# untitled.net
KiCad netlist of a schematic drawn in EAGLE
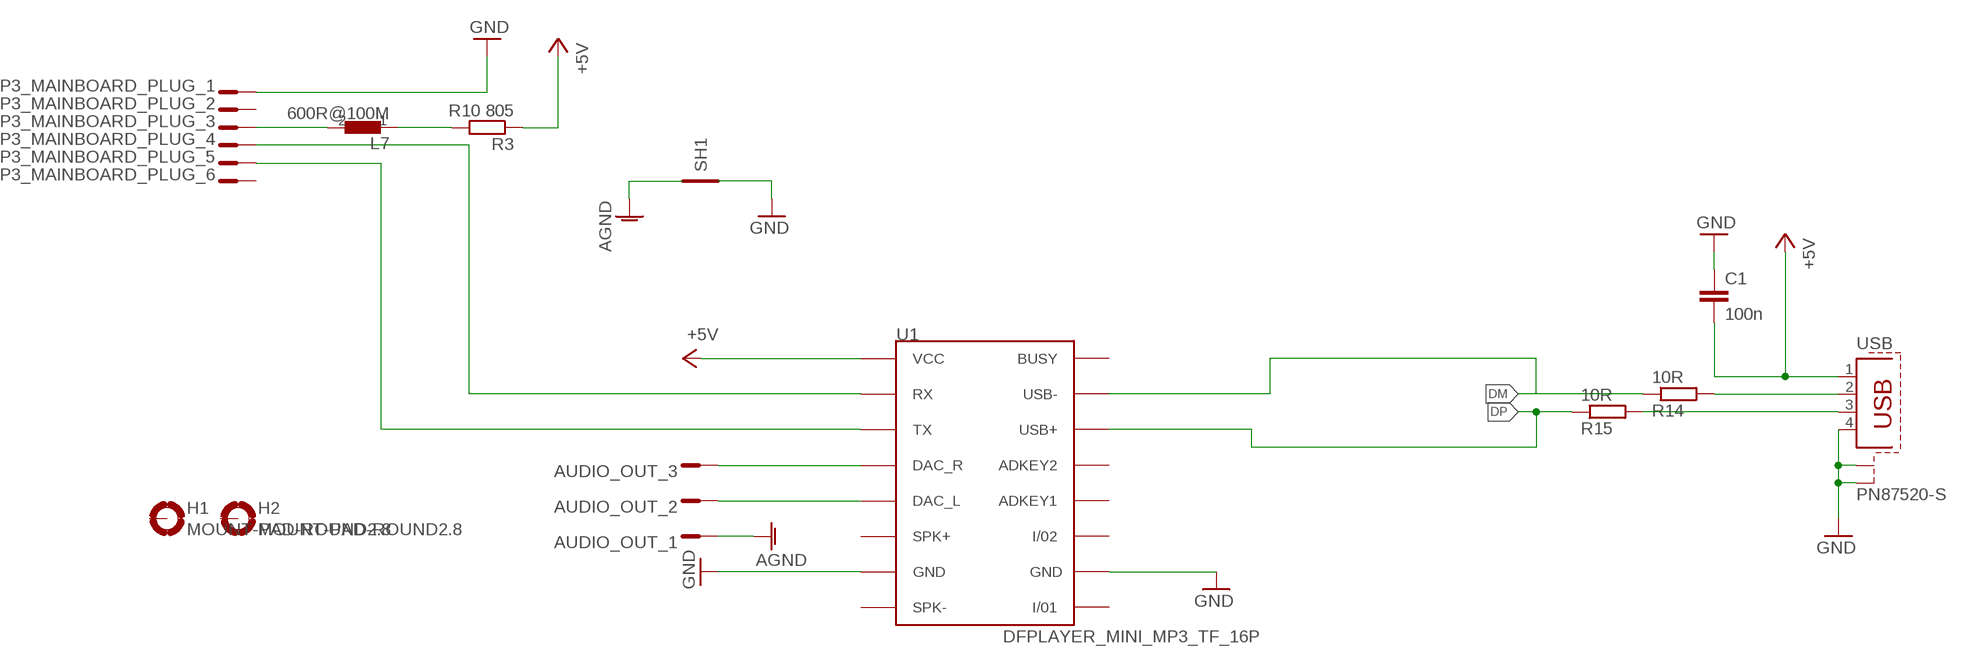
[diagram p0: schematic, sheet 1]

(export (version "E")
  (design (tool "Eeschema 10.0.6"))
  (components
    (comp (ref "AUDIO_OUT")
      (value "JST_3_PIN_B3B-PH-KS")
      (footprint "eagle-import:B3B-PH-KS")
      (libsource (lib "eagle-import") (part "JST_3_PIN_B3B-PH-KS"))
    )
    (comp (ref "C1")
      (value "100n")
      (footprint "eagle-import:C0805")
      (libsource (lib "eagle-import") (part "C-EUC0805"))
    )
    (comp (ref "H1")
      (value "MOUNT-PAD-ROUND2.8")
      (footprint "eagle-import:2,8-PAD")
      (libsource (lib "eagle-import") (part "MOUNT-PAD-ROUND2.8"))
    )
    (comp (ref "H2")
      (value "MOUNT-PAD-ROUND2.8")
      (footprint "eagle-import:2,8-PAD")
      (libsource (lib "eagle-import") (part "MOUNT-PAD-ROUND2.8"))
    )
    (comp (ref "L7")
      (value "600R@100M")
      (footprint "eagle-import:R0805")
      (libsource (lib "eagle-import") (part "FERRITR0805"))
    )
    (comp (ref "MP3_MAINBOARD_PLUG")
      (value "JST_6_PIN_B6B-PH-KS")
      (footprint "eagle-import:B6B-PH-KS")
      (libsource (lib "eagle-import") (part "JST_6_PIN_B6B-PH-KS"))
    )
    (comp (ref "R3")
      (value "R10 805")
      (footprint "eagle-import:R0805")
      (libsource (lib "eagle-import") (part "R-EU_R0805"))
    )
    (comp (ref "R14")
      (value "10R")
      (footprint "eagle-import:R0805")
      (libsource (lib "eagle-import") (part "R-EU_R0805"))
    )
    (comp (ref "R15")
      (value "10R")
      (footprint "eagle-import:R0805")
      (libsource (lib "eagle-import") (part "R-EU_R0805"))
    )
    (comp (ref "SH1")
      (value "SHORT-V12_MILS")
      (footprint "eagle-import:12_MILS")
      (libsource (lib "eagle-import") (part "SHORT-V12_MILS"))
    )
    (comp (ref "U1")
      (value "DFPLAYER_MINI_MP3_TF_16P")
      (footprint "eagle-import:20_5M_SQUARE")
      (libsource (lib "eagle-import") (part "DFPLAYER_MINI_MP3_TF_16P"))
    )
    (comp (ref "USB")
      (value "PN87520-S")
      (footprint "eagle-import:PN87520-S")
      (libsource (lib "eagle-import") (part "PN87520-S"))
    )
  )
  (nets
    (net (code "1") (name "+5V") (class "Default")
      (node (ref "C1") (pin "2") (pinfunction "2_2") (pintype "passive"))
      (node (ref "R3") (pin "1") (pinfunction "1_1") (pintype "passive"))
      (node (ref "U1") (pin "P$1") (pinfunction "VCC_P$1") (pintype "bidirectional"))
      (node (ref "USB") (pin "1") (pinfunction "1_1") (pintype "passive"))
    )
    (net (code "2") (name "AGND") (class "Default")
      (node (ref "AUDIO_OUT") (pin "P$1") (pinfunction "P$1_P$1") (pintype "bidirectional"))
      (node (ref "SH1") (pin "P$2") (pinfunction "P$2_P$2") (pintype "bidirectional"))
    )
    (net (code "3") (name "DM") (class "Default")
      (node (ref "R14") (pin "1") (pinfunction "1_1") (pintype "passive"))
      (node (ref "U1") (pin "P$15") (pinfunction "USB-_P$15") (pintype "bidirectional"))
    )
    (net (code "4") (name "DP") (class "Default")
      (node (ref "R15") (pin "1") (pinfunction "1_1") (pintype "passive"))
      (node (ref "U1") (pin "P$14") (pinfunction "USB+_P$14") (pintype "bidirectional"))
    )
    (net (code "5") (name "GND") (class "Default")
      (node (ref "C1") (pin "1") (pinfunction "1_1") (pintype "passive"))
      (node (ref "MP3_MAINBOARD_PLUG") (pin "P$1") (pinfunction "P$1_P$1") (pintype "bidirectional"))
      (node (ref "SH1") (pin "P$1") (pinfunction "P$1_P$1") (pintype "bidirectional"))
      (node (ref "U1") (pin "P$10") (pinfunction "GND1_P$10") (pintype "bidirectional"))
      (node (ref "U1") (pin "P$7") (pinfunction "GND_P$7") (pintype "bidirectional"))
      (node (ref "USB") (pin "4") (pinfunction "4_4") (pintype "passive"))
      (node (ref "USB") (pin "S1") (pinfunction "S1_S1") (pintype "passive"))
      (node (ref "USB") (pin "S2") (pinfunction "S2_S2") (pintype "passive"))
    )
    (net (code "6") (name "Net-(AUDIO_OUTB-P$1)") (class "Default")
      (node (ref "AUDIO_OUT") (pin "P$2") (pinfunction "P$1_P$2") (pintype "bidirectional"))
      (node (ref "U1") (pin "P$5") (pinfunction "DAC_L_P$5") (pintype "bidirectional"))
    )
    (net (code "7") (name "Net-(AUDIO_OUTC-P$1)") (class "Default")
      (node (ref "AUDIO_OUT") (pin "P$3") (pinfunction "P$1_P$3") (pintype "bidirectional"))
      (node (ref "U1") (pin "P$4") (pinfunction "DAC_R_P$4") (pintype "bidirectional"))
    )
    (net (code "8") (name "Net-(L7-Pad1)") (class "Default")
      (node (ref "L7") (pin "1") (pinfunction "1_1") (pintype "passive"))
      (node (ref "R3") (pin "2") (pinfunction "2_2") (pintype "passive"))
    )
    (net (code "9") (name "Net-(MP3_MAINBOARD_PLUGC-P$1)") (class "Default")
      (node (ref "L7") (pin "2") (pinfunction "2_2") (pintype "passive"))
      (node (ref "MP3_MAINBOARD_PLUG") (pin "P$3") (pinfunction "P$1_P$3") (pintype "bidirectional"))
    )
    (net (code "10") (name "Net-(MP3_MAINBOARD_PLUGD-P$1)") (class "Default")
      (node (ref "MP3_MAINBOARD_PLUG") (pin "P$4") (pinfunction "P$1_P$4") (pintype "bidirectional"))
      (node (ref "U1") (pin "P$2") (pinfunction "RX_P$2") (pintype "bidirectional"))
    )
    (net (code "11") (name "Net-(MP3_MAINBOARD_PLUGE-P$1)") (class "Default")
      (node (ref "MP3_MAINBOARD_PLUG") (pin "P$5") (pinfunction "P$1_P$5") (pintype "bidirectional"))
      (node (ref "U1") (pin "P$3") (pinfunction "TX_P$3") (pintype "bidirectional"))
    )
    (net (code "12") (name "Net-(R14-Pad2)") (class "Default")
      (node (ref "R14") (pin "2") (pinfunction "2_2") (pintype "passive"))
      (node (ref "USB") (pin "2") (pinfunction "2_2") (pintype "passive"))
    )
    (net (code "13") (name "Net-(R15-Pad2)") (class "Default")
      (node (ref "R15") (pin "2") (pinfunction "2_2") (pintype "passive"))
      (node (ref "USB") (pin "3") (pinfunction "3_3") (pintype "passive"))
    )
    (net (code "14") (name "unconnected-(H1-MOUNT-PadB2,8)") (class "Default")
      (node (ref "H1") (pin "B2,8") (pinfunction "MOUNT_B2,8") (pintype "passive"))
    )
    (net (code "15") (name "unconnected-(H2-MOUNT-PadB2,8)") (class "Default")
      (node (ref "H2") (pin "B2,8") (pinfunction "MOUNT_B2,8") (pintype "passive"))
    )
    (net (code "16") (name "unconnected-(MP3_MAINBOARD_PLUGB-P$1-PadP$2)") (class "Default")
      (node (ref "MP3_MAINBOARD_PLUG") (pin "P$2") (pinfunction "P$1_P$2") (pintype "bidirectional"))
    )
    (net (code "17") (name "unconnected-(MP3_MAINBOARD_PLUGF-P$1-PadP$6)") (class "Default")
      (node (ref "MP3_MAINBOARD_PLUG") (pin "P$6") (pinfunction "P$1_P$6") (pintype "bidirectional"))
    )
    (net (code "18") (name "unconnected-(U1-ADKEY1-PadP$12)") (class "Default")
      (node (ref "U1") (pin "P$12") (pinfunction "ADKEY1_P$12") (pintype "bidirectional"))
    )
    (net (code "19") (name "unconnected-(U1-ADKEY2-PadP$13)") (class "Default")
      (node (ref "U1") (pin "P$13") (pinfunction "ADKEY2_P$13") (pintype "bidirectional"))
    )
    (net (code "20") (name "unconnected-(U1-BUSY-PadP$16)") (class "Default")
      (node (ref "U1") (pin "P$16") (pinfunction "BUSY_P$16") (pintype "bidirectional"))
    )
    (net (code "21") (name "unconnected-(U1-I{slash}01-PadP$9)") (class "Default")
      (node (ref "U1") (pin "P$9") (pinfunction "I/01_P$9") (pintype "bidirectional"))
    )
    (net (code "22") (name "unconnected-(U1-I{slash}02-PadP$11)") (class "Default")
      (node (ref "U1") (pin "P$11") (pinfunction "I/02_P$11") (pintype "bidirectional"))
    )
    (net (code "23") (name "unconnected-(U1-SPK+-PadP$6)") (class "Default")
      (node (ref "U1") (pin "P$6") (pinfunction "SPK+_P$6") (pintype "bidirectional"))
    )
    (net (code "24") (name "unconnected-(U1-SPK--PadP$8)") (class "Default")
      (node (ref "U1") (pin "P$8") (pinfunction "SPK-_P$8") (pintype "bidirectional"))
    )
  )
)
